# COUNTER.net
KiCad netlist of a schematic drawn in Altium Designer
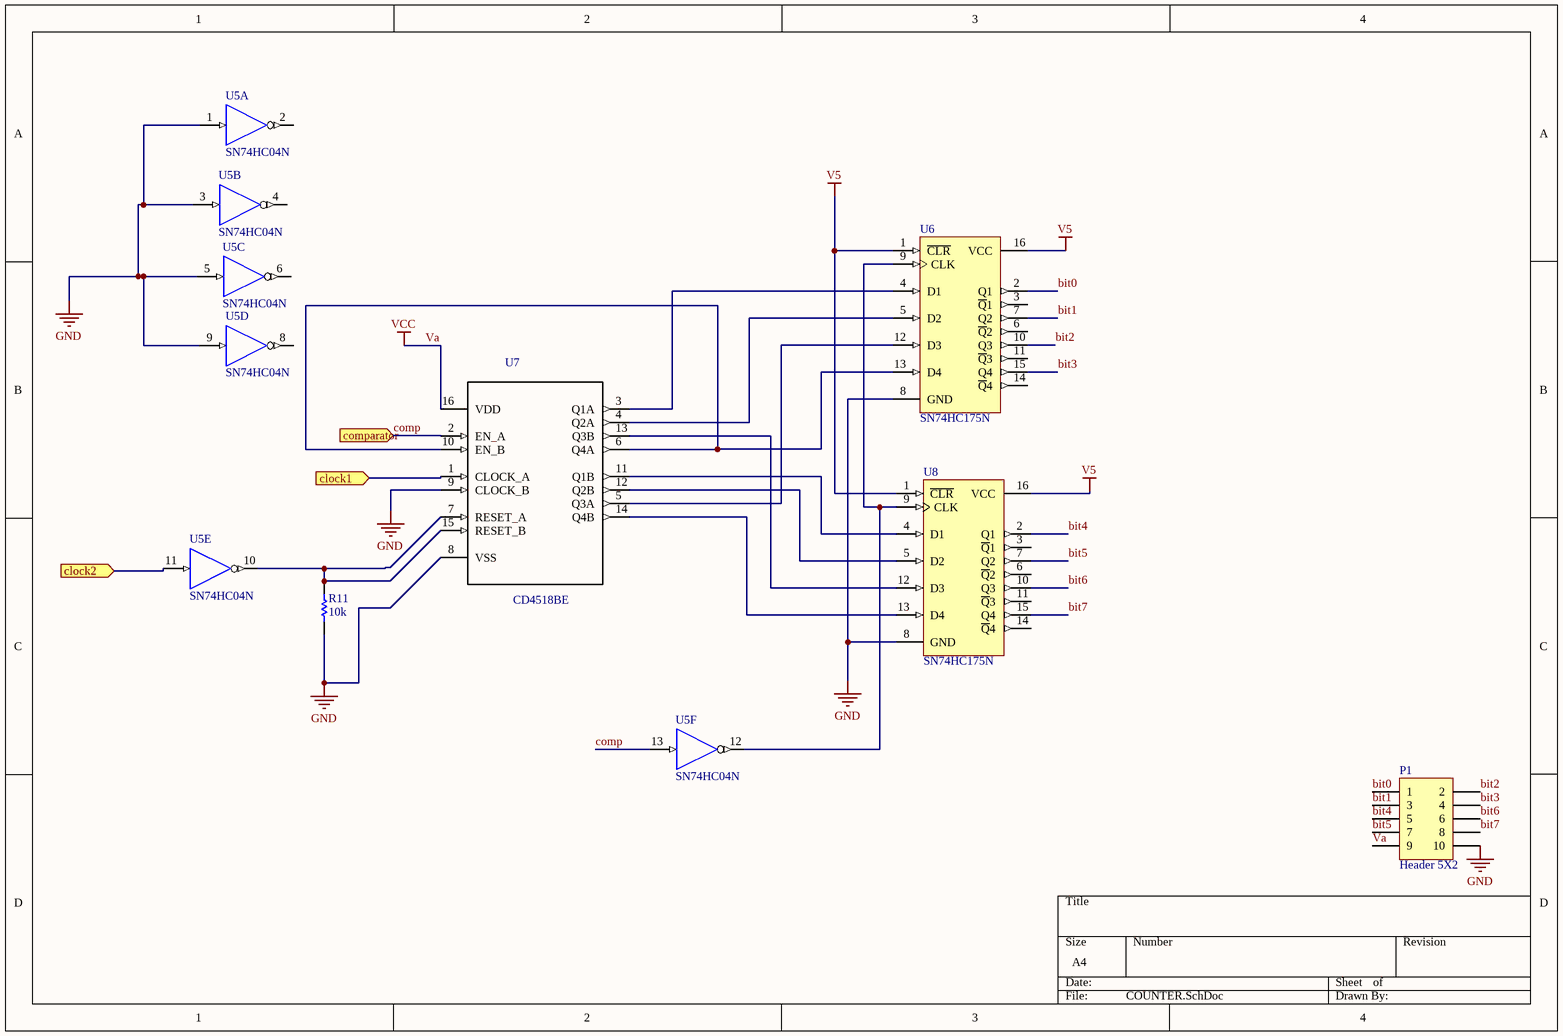
[diagram p0: COUNTER.SchDoc]

(export (version "E")
  (design (tool "Eeschema 10.0.6"))
  (components
    (comp (ref "P1")
      (value "Header 5X2")
      (footprint "HDR2X5")
      (description "Header, 5-Pin, Dual row")
      (fields (field (name "PUBLISHER") "Altium Limited"))
      (libsource (lib "Miscellaneous Connectors") (part "Header 5X2"))
    )
    (comp (ref "R11") (value "10k") (footprint "RES400") (libsource (lib "LIBEBAL") (part "RES")))
    (comp (ref "U5")
      (value "SN74HC04N")
      (footprint "N014")
      (description "Hex Inverter")
      (fields (field (name "PUBLISHER") "Altium Limited"))
      (libsource (lib "TI Logic Gate 2") (part "SN74HC04N"))
    )
    (comp (ref "U6")
      (value "SN74HC175N")
      (footprint "N016")
      (description "Quadruple D-Type Flip-Flop with Clear")
      (fields (field (name "PUBLISHER") "Altium Limited"))
      (libsource (lib "TI Logic Flip-Flop") (part "SN74HC175N"))
    )
    (comp (ref "U7")
      (value "CD4518BE")
      (footprint "*DIP254P762X508-16")
      (fields (field (name "DIGI-KEY_PART_NUMBER") "296-2076-5-ND") (field (name "MF") "Texas Instruments"))
      (libsource (lib "CD4518BE") (part "CD4518BE"))
    )
    (comp (ref "U8")
      (value "SN74HC175N")
      (footprint "N016")
      (description "Quadruple D-Type Flip-Flop with Clear")
      (fields (field (name "PUBLISHER") "Altium Limited"))
      (libsource (lib "TI Logic Flip-Flop") (part "SN74HC175N"))
    )
  )
  (nets
    (net (code "1") (name "/bit0") (class "Default")
      (node (ref "P1") (pin "1") (pinfunction "1_1") (pintype "passive"))
      (node (ref "U6") (pin "2") (pinfunction "Q1_2") (pintype "output"))
    )
    (net (code "2") (name "/bit1") (class "Default")
      (node (ref "P1") (pin "3") (pinfunction "3_3") (pintype "passive"))
      (node (ref "U6") (pin "7") (pinfunction "Q2_7") (pintype "output"))
    )
    (net (code "3") (name "/bit2") (class "Default")
      (node (ref "P1") (pin "2") (pinfunction "2_2") (pintype "passive"))
      (node (ref "U6") (pin "10") (pinfunction "Q3_10") (pintype "output"))
    )
    (net (code "4") (name "/bit3") (class "Default")
      (node (ref "P1") (pin "4") (pinfunction "4_4") (pintype "passive"))
      (node (ref "U6") (pin "15") (pinfunction "Q4_15") (pintype "output"))
    )
    (net (code "5") (name "/bit4") (class "Default")
      (node (ref "P1") (pin "5") (pinfunction "5_5") (pintype "passive"))
      (node (ref "U8") (pin "2") (pinfunction "Q1_2") (pintype "output"))
    )
    (net (code "6") (name "/bit5") (class "Default")
      (node (ref "P1") (pin "7") (pinfunction "7_7") (pintype "passive"))
      (node (ref "U8") (pin "7") (pinfunction "Q2_7") (pintype "output"))
    )
    (net (code "7") (name "/bit6") (class "Default")
      (node (ref "P1") (pin "6") (pinfunction "6_6") (pintype "passive"))
      (node (ref "U8") (pin "10") (pinfunction "Q3_10") (pintype "output"))
    )
    (net (code "8") (name "/bit7") (class "Default")
      (node (ref "P1") (pin "8") (pinfunction "8_8") (pintype "passive"))
      (node (ref "U8") (pin "15") (pinfunction "Q4_15") (pintype "output"))
    )
    (net (code "9") (name "/clock1") (class "Default")
      (node (ref "U7") (pin "1") (pinfunction "CLOCK_A_1") (pintype "input"))
    )
    (net (code "10") (name "/clock2") (class "Default")
      (node (ref "U5") (pin "11") (pinfunction "A_11") (pintype "input"))
    )
    (net (code "11") (name "/comp") (class "Default")
      (node (ref "U5") (pin "13") (pinfunction "A_13") (pintype "input"))
      (node (ref "U7") (pin "2") (pinfunction "EN_A_2") (pintype "input"))
    )
    (net (code "12") (name "GND") (class "Default")
      (node (ref "P1") (pin "10") (pinfunction "10_10") (pintype "passive"))
      (node (ref "R11") (pin "1") (pinfunction "1_1") (pintype "passive"))
      (node (ref "U5") (pin "1") (pinfunction "A_1") (pintype "input"))
      (node (ref "U5") (pin "3") (pinfunction "A_3") (pintype "input"))
      (node (ref "U5") (pin "5") (pinfunction "A_5") (pintype "input"))
      (node (ref "U5") (pin "7") (pinfunction "GND_7") (pintype "power_in"))
      (node (ref "U5") (pin "9") (pinfunction "A_9") (pintype "input"))
      (node (ref "U6") (pin "8") (pinfunction "GND_8") (pintype "power_in"))
      (node (ref "U7") (pin "8") (pinfunction "VSS_8") (pintype "power_in"))
      (node (ref "U7") (pin "9") (pinfunction "CLOCK_B_9") (pintype "input"))
      (node (ref "U8") (pin "8") (pinfunction "GND_8") (pintype "power_in"))
    )
    (net (code "13") (name "Net-(U5E-Y)") (class "Default")
      (node (ref "R11") (pin "2") (pinfunction "2_2") (pintype "passive"))
      (node (ref "U5") (pin "10") (pinfunction "Y_10") (pintype "output"))
      (node (ref "U7") (pin "15") (pinfunction "RESET_B_15") (pintype "input"))
      (node (ref "U7") (pin "7") (pinfunction "RESET_A_7") (pintype "input"))
    )
    (net (code "14") (name "Net-(U5F-Y)") (class "Default")
      (node (ref "U5") (pin "12") (pinfunction "Y_12") (pintype "output"))
      (node (ref "U6") (pin "9") (pinfunction "CLK_9") (pintype "input"))
      (node (ref "U8") (pin "9") (pinfunction "CLK_9") (pintype "input"))
    )
    (net (code "15") (name "Net-(U6-D1)") (class "Default")
      (node (ref "U6") (pin "4") (pinfunction "D1_4") (pintype "input"))
      (node (ref "U7") (pin "3") (pinfunction "Q1A_3") (pintype "output"))
    )
    (net (code "16") (name "Net-(U6-D2)") (class "Default")
      (node (ref "U6") (pin "5") (pinfunction "D2_5") (pintype "input"))
      (node (ref "U7") (pin "4") (pinfunction "Q2A_4") (pintype "output"))
    )
    (net (code "17") (name "Net-(U6-D3)") (class "Default")
      (node (ref "U6") (pin "12") (pinfunction "D3_12") (pintype "input"))
      (node (ref "U7") (pin "5") (pinfunction "Q3A_5") (pintype "output"))
    )
    (net (code "18") (name "Net-(U6-D4)") (class "Default")
      (node (ref "U6") (pin "13") (pinfunction "D4_13") (pintype "input"))
      (node (ref "U7") (pin "10") (pinfunction "EN_B_10") (pintype "input"))
      (node (ref "U7") (pin "6") (pinfunction "Q4A_6") (pintype "output"))
    )
    (net (code "19") (name "Net-(U7-Q1B)") (class "Default")
      (node (ref "U7") (pin "11") (pinfunction "Q1B_11") (pintype "output"))
      (node (ref "U8") (pin "4") (pinfunction "D1_4") (pintype "input"))
    )
    (net (code "20") (name "Net-(U7-Q2B)") (class "Default")
      (node (ref "U7") (pin "12") (pinfunction "Q2B_12") (pintype "output"))
      (node (ref "U8") (pin "5") (pinfunction "D2_5") (pintype "input"))
    )
    (net (code "21") (name "Net-(U7-Q3B)") (class "Default")
      (node (ref "U7") (pin "13") (pinfunction "Q3B_13") (pintype "output"))
      (node (ref "U8") (pin "12") (pinfunction "D3_12") (pintype "input"))
    )
    (net (code "22") (name "Net-(U7-Q4B)") (class "Default")
      (node (ref "U7") (pin "14") (pinfunction "Q4B_14") (pintype "output"))
      (node (ref "U8") (pin "13") (pinfunction "D4_13") (pintype "input"))
    )
    (net (code "23") (name "V5") (class "Default")
      (node (ref "U5") (pin "14") (pinfunction "V5_14") (pintype "power_in"))
      (node (ref "U6") (pin "1") (pinfunction "~{CLR}_1") (pintype "input"))
      (node (ref "U6") (pin "16") (pinfunction "VCC_16") (pintype "power_in"))
      (node (ref "U8") (pin "1") (pinfunction "~{CLR}_1") (pintype "input"))
      (node (ref "U8") (pin "16") (pinfunction "VCC_16") (pintype "power_in"))
    )
    (net (code "24") (name "VCC") (class "Default")
      (node (ref "P1") (pin "9") (pinfunction "9_9") (pintype "passive"))
      (node (ref "U7") (pin "16") (pinfunction "VDD_16") (pintype "power_in"))
    )
    (net (code "25") (name "unconnected-(U5A-Y-Pad2)") (class "Default")
      (node (ref "U5") (pin "2") (pinfunction "Y_2") (pintype "output"))
    )
    (net (code "26") (name "unconnected-(U5B-Y-Pad4)") (class "Default")
      (node (ref "U5") (pin "4") (pinfunction "Y_4") (pintype "output"))
    )
    (net (code "27") (name "unconnected-(U5C-Y-Pad6)") (class "Default")
      (node (ref "U5") (pin "6") (pinfunction "Y_6") (pintype "output"))
    )
    (net (code "28") (name "unconnected-(U5D-Y-Pad8)") (class "Default")
      (node (ref "U5") (pin "8") (pinfunction "Y_8") (pintype "output"))
    )
    (net (code "29") (name "unconnected-(U6-~{Q}1-Pad3)") (class "Default")
      (node (ref "U6") (pin "3") (pinfunction "~{Q}1_3") (pintype "output"))
    )
    (net (code "30") (name "unconnected-(U6-~{Q}2-Pad6)") (class "Default")
      (node (ref "U6") (pin "6") (pinfunction "~{Q}2_6") (pintype "output"))
    )
    (net (code "31") (name "unconnected-(U6-~{Q}3-Pad11)") (class "Default")
      (node (ref "U6") (pin "11") (pinfunction "~{Q}3_11") (pintype "output"))
    )
    (net (code "32") (name "unconnected-(U6-~{Q}4-Pad14)") (class "Default")
      (node (ref "U6") (pin "14") (pinfunction "~{Q}4_14") (pintype "output"))
    )
    (net (code "33") (name "unconnected-(U8-~{Q}1-Pad3)") (class "Default")
      (node (ref "U8") (pin "3") (pinfunction "~{Q}1_3") (pintype "output"))
    )
    (net (code "34") (name "unconnected-(U8-~{Q}2-Pad6)") (class "Default")
      (node (ref "U8") (pin "6") (pinfunction "~{Q}2_6") (pintype "output"))
    )
    (net (code "35") (name "unconnected-(U8-~{Q}3-Pad11)") (class "Default")
      (node (ref "U8") (pin "11") (pinfunction "~{Q}3_11") (pintype "output"))
    )
    (net (code "36") (name "unconnected-(U8-~{Q}4-Pad14)") (class "Default")
      (node (ref "U8") (pin "14") (pinfunction "~{Q}4_14") (pintype "output"))
    )
  )
)
